# InterfacesB_RGMII_Ethernet.net
KiCad netlist of a schematic drawn in Altium Designer
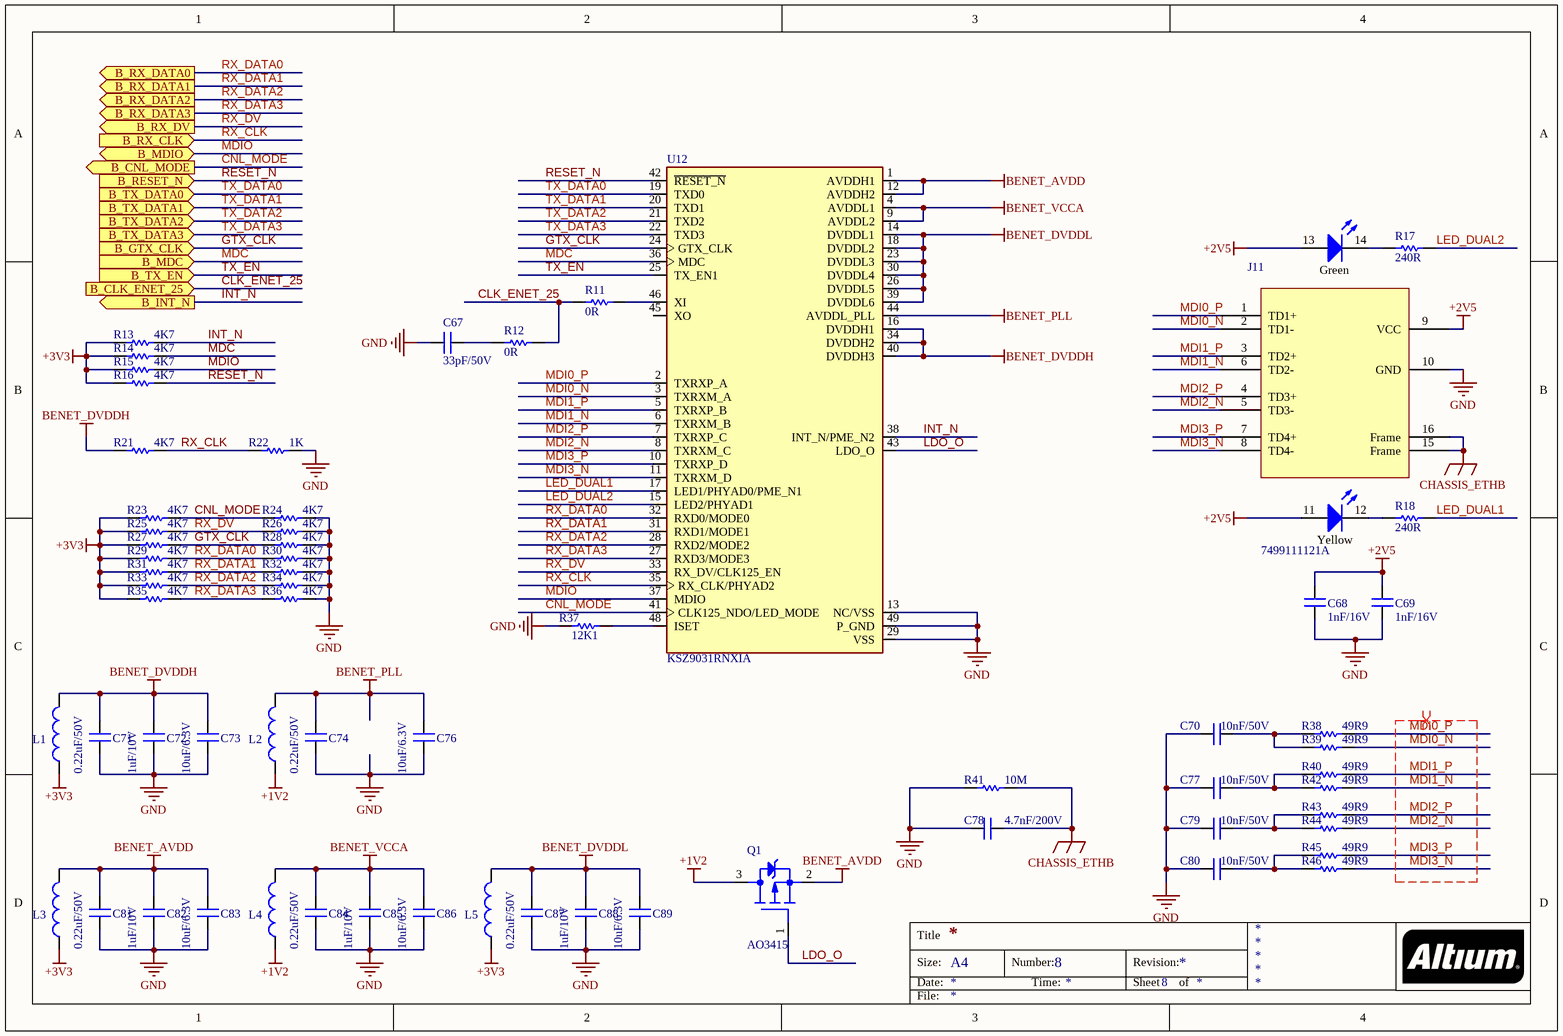
[diagram p0: InterfacesB_RGMII_Ethernet.SchDoc]

(export (version "E")
  (design (tool "Eeschema 10.0.6"))
  (components
    (comp (ref "C67")
      (value "33pF/50V")
      (footprint "CAP_0805")
      (fields (field (name "Comment") "CAP_0805"))
      (libsource (lib "AdapterLib") (part "CAP_0805"))
    )
    (comp (ref "C68")
      (value "1nF/16V")
      (footprint "CAP_0805")
      (fields (field (name "Comment") "CAP_0805"))
      (libsource (lib "AdapterLib") (part "CAP_0805"))
    )
    (comp (ref "C69")
      (value "1nF/16V")
      (footprint "CAP_0805")
      (fields (field (name "Comment") "CAP_0805"))
      (libsource (lib "AdapterLib") (part "CAP_0805"))
    )
    (comp (ref "C70")
      (value "10nF/50V")
      (footprint "CAP_0805")
      (fields (field (name "Comment") "CAP_0805"))
      (libsource (lib "AdapterLib") (part "CAP_0805"))
    )
    (comp (ref "C71")
      (value "0.22uF/50V")
      (footprint "CAP_0805")
      (fields (field (name "Comment") "CAP_0805"))
      (libsource (lib "AdapterLib") (part "CAP_0805"))
    )
    (comp (ref "C72")
      (value "1uF/10V")
      (footprint "CAP_0805")
      (fields (field (name "Comment") "CAP_0805"))
      (libsource (lib "AdapterLib") (part "CAP_0805"))
    )
    (comp (ref "C73")
      (value "10uF/6.3V")
      (footprint "CAP_0805")
      (fields (field (name "Comment") "CAP_0805"))
      (libsource (lib "AdapterLib") (part "CAP_0805"))
    )
    (comp (ref "C74")
      (value "0.22uF/50V")
      (footprint "CAP_0805")
      (fields (field (name "Comment") "CAP_0805"))
      (libsource (lib "AdapterLib") (part "CAP_0805"))
    )
    (comp (ref "C76")
      (value "10uF/6.3V")
      (footprint "CAP_0805")
      (fields (field (name "Comment") "CAP_0805"))
      (libsource (lib "AdapterLib") (part "CAP_0805"))
    )
    (comp (ref "C77")
      (value "10nF/50V")
      (footprint "CAP_0805")
      (fields (field (name "Comment") "CAP_0805"))
      (libsource (lib "AdapterLib") (part "CAP_0805"))
    )
    (comp (ref "C78")
      (value "4.7nF/200V")
      (footprint "CAP_0805")
      (fields (field (name "Comment") "CAP_0805"))
      (libsource (lib "AdapterLib") (part "CAP_0805"))
    )
    (comp (ref "C79")
      (value "10nF/50V")
      (footprint "CAP_0805")
      (fields (field (name "Comment") "CAP_0805"))
      (libsource (lib "AdapterLib") (part "CAP_0805"))
    )
    (comp (ref "C80")
      (value "10nF/50V")
      (footprint "CAP_0805")
      (fields (field (name "Comment") "CAP_0805"))
      (libsource (lib "AdapterLib") (part "CAP_0805"))
    )
    (comp (ref "C81")
      (value "0.22uF/50V")
      (footprint "CAP_0805")
      (fields (field (name "Comment") "CAP_0805"))
      (libsource (lib "AdapterLib") (part "CAP_0805"))
    )
    (comp (ref "C82")
      (value "1uF/10V")
      (footprint "CAP_0805")
      (fields (field (name "Comment") "CAP_0805"))
      (libsource (lib "AdapterLib") (part "CAP_0805"))
    )
    (comp (ref "C83")
      (value "10uF/6.3V")
      (footprint "CAP_0805")
      (fields (field (name "Comment") "CAP_0805"))
      (libsource (lib "AdapterLib") (part "CAP_0805"))
    )
    (comp (ref "C84")
      (value "0.22uF/50V")
      (footprint "CAP_0805")
      (fields (field (name "Comment") "CAP_0805"))
      (libsource (lib "AdapterLib") (part "CAP_0805"))
    )
    (comp (ref "C85")
      (value "1uF/10V")
      (footprint "CAP_0805")
      (fields (field (name "Comment") "CAP_0805"))
      (libsource (lib "AdapterLib") (part "CAP_0805"))
    )
    (comp (ref "C86")
      (value "10uF/6.3V")
      (footprint "CAP_0805")
      (fields (field (name "Comment") "CAP_0805"))
      (libsource (lib "AdapterLib") (part "CAP_0805"))
    )
    (comp (ref "C87")
      (value "0.22uF/50V")
      (footprint "CAP_0805")
      (fields (field (name "Comment") "CAP_0805"))
      (libsource (lib "AdapterLib") (part "CAP_0805"))
    )
    (comp (ref "C88")
      (value "1uF/10V")
      (footprint "CAP_0805")
      (fields (field (name "Comment") "CAP_0805"))
      (libsource (lib "AdapterLib") (part "CAP_0805"))
    )
    (comp (ref "C89")
      (value "10uF/6.3V")
      (footprint "CAP_0805")
      (fields (field (name "Comment") "CAP_0805"))
      (libsource (lib "AdapterLib") (part "CAP_0805"))
    )
    (comp (ref "J11")
      (value "7499111121A")
      (footprint "7499111121A")
      (libsource (lib "AdapterLib") (part "7499111121A"))
    )
    (comp (ref "L1")
      (value "IND_0805")
      (footprint "IND_0805")
      (libsource (lib "AdapterLib") (part "IND_0805"))
    )
    (comp (ref "L2")
      (value "IND_0805")
      (footprint "IND_0805")
      (libsource (lib "AdapterLib") (part "IND_0805"))
    )
    (comp (ref "L3")
      (value "IND_0805")
      (footprint "IND_0805")
      (libsource (lib "AdapterLib") (part "IND_0805"))
    )
    (comp (ref "L4")
      (value "IND_0805")
      (footprint "IND_0805")
      (libsource (lib "AdapterLib") (part "IND_0805"))
    )
    (comp (ref "L5")
      (value "IND_0805")
      (footprint "IND_0805")
      (libsource (lib "AdapterLib") (part "IND_0805"))
    )
    (comp (ref "Q1")
      (value "AO3415")
      (footprint "AO3415")
      (description "20V P-Channel MOSFET")
      (libsource (lib "AdapterLib") (part "AO3415"))
    )
    (comp (ref "R11")
      (value "0R")
      (footprint "RES_0805")
      (fields (field (name "Comment") "RES_0805"))
      (libsource (lib "AdapterLib") (part "RES_0805"))
    )
    (comp (ref "R12")
      (value "0R")
      (footprint "RES_0805")
      (fields (field (name "Comment") "RES_0805"))
      (libsource (lib "AdapterLib") (part "RES_0805"))
    )
    (comp (ref "R13")
      (value "4K7")
      (footprint "RES_0805")
      (fields (field (name "Comment") "RES_0805"))
      (libsource (lib "AdapterLib") (part "RES_0805"))
    )
    (comp (ref "R14")
      (value "4K7")
      (footprint "RES_0805")
      (fields (field (name "Comment") "RES_0805"))
      (libsource (lib "AdapterLib") (part "RES_0805"))
    )
    (comp (ref "R15")
      (value "4K7")
      (footprint "RES_0805")
      (fields (field (name "Comment") "RES_0805"))
      (libsource (lib "AdapterLib") (part "RES_0805"))
    )
    (comp (ref "R16")
      (value "4K7")
      (footprint "RES_0805")
      (fields (field (name "Comment") "RES_0805"))
      (libsource (lib "AdapterLib") (part "RES_0805"))
    )
    (comp (ref "R17")
      (value "240R")
      (footprint "RES_0805")
      (fields (field (name "Comment") "RES_0805"))
      (libsource (lib "AdapterLib") (part "RES_0805"))
    )
    (comp (ref "R18")
      (value "240R")
      (footprint "RES_0805")
      (fields (field (name "Comment") "RES_0805"))
      (libsource (lib "AdapterLib") (part "RES_0805"))
    )
    (comp (ref "R21")
      (value "4K7")
      (footprint "RES_0805")
      (fields (field (name "Comment") "RES_0805"))
      (libsource (lib "AdapterLib") (part "RES_0805"))
    )
    (comp (ref "R22")
      (value "1K")
      (footprint "RES_0805")
      (fields (field (name "Comment") "RES_0805"))
      (libsource (lib "AdapterLib") (part "RES_0805"))
    )
    (comp (ref "R23")
      (value "4K7")
      (footprint "RES_0805")
      (fields (field (name "Comment") "RES_0805"))
      (libsource (lib "AdapterLib") (part "RES_0805"))
    )
    (comp (ref "R24")
      (value "4K7")
      (footprint "RES_0805")
      (fields (field (name "Comment") "RES_0805"))
      (libsource (lib "AdapterLib") (part "RES_0805"))
    )
    (comp (ref "R25")
      (value "4K7")
      (footprint "RES_0805")
      (fields (field (name "Comment") "RES_0805"))
      (libsource (lib "AdapterLib") (part "RES_0805"))
    )
    (comp (ref "R26")
      (value "4K7")
      (footprint "RES_0805")
      (fields (field (name "Comment") "RES_0805"))
      (libsource (lib "AdapterLib") (part "RES_0805"))
    )
    (comp (ref "R27")
      (value "4K7")
      (footprint "RES_0805")
      (fields (field (name "Comment") "RES_0805"))
      (libsource (lib "AdapterLib") (part "RES_0805"))
    )
    (comp (ref "R28")
      (value "4K7")
      (footprint "RES_0805")
      (fields (field (name "Comment") "RES_0805"))
      (libsource (lib "AdapterLib") (part "RES_0805"))
    )
    (comp (ref "R29")
      (value "4K7")
      (footprint "RES_0805")
      (fields (field (name "Comment") "RES_0805"))
      (libsource (lib "AdapterLib") (part "RES_0805"))
    )
    (comp (ref "R30")
      (value "4K7")
      (footprint "RES_0805")
      (fields (field (name "Comment") "RES_0805"))
      (libsource (lib "AdapterLib") (part "RES_0805"))
    )
    (comp (ref "R31")
      (value "4K7")
      (footprint "RES_0805")
      (fields (field (name "Comment") "RES_0805"))
      (libsource (lib "AdapterLib") (part "RES_0805"))
    )
    (comp (ref "R32")
      (value "4K7")
      (footprint "RES_0805")
      (fields (field (name "Comment") "RES_0805"))
      (libsource (lib "AdapterLib") (part "RES_0805"))
    )
    (comp (ref "R33")
      (value "4K7")
      (footprint "RES_0805")
      (fields (field (name "Comment") "RES_0805"))
      (libsource (lib "AdapterLib") (part "RES_0805"))
    )
    (comp (ref "R34")
      (value "4K7")
      (footprint "RES_0805")
      (fields (field (name "Comment") "RES_0805"))
      (libsource (lib "AdapterLib") (part "RES_0805"))
    )
    (comp (ref "R35")
      (value "4K7")
      (footprint "RES_0805")
      (fields (field (name "Comment") "RES_0805"))
      (libsource (lib "AdapterLib") (part "RES_0805"))
    )
    (comp (ref "R36")
      (value "4K7")
      (footprint "RES_0805")
      (fields (field (name "Comment") "RES_0805"))
      (libsource (lib "AdapterLib") (part "RES_0805"))
    )
    (comp (ref "R37")
      (value "12K1")
      (footprint "RES_0805")
      (fields (field (name "Comment") "RES_0805"))
      (libsource (lib "AdapterLib") (part "RES_0805"))
    )
    (comp (ref "R38")
      (value "49R9")
      (footprint "RES_0805")
      (fields (field (name "Comment") "RES_0805"))
      (libsource (lib "AdapterLib") (part "RES_0805"))
    )
    (comp (ref "R39")
      (value "49R9")
      (footprint "RES_0805")
      (fields (field (name "Comment") "RES_0805"))
      (libsource (lib "AdapterLib") (part "RES_0805"))
    )
    (comp (ref "R40")
      (value "49R9")
      (footprint "RES_0805")
      (fields (field (name "Comment") "RES_0805"))
      (libsource (lib "AdapterLib") (part "RES_0805"))
    )
    (comp (ref "R41")
      (value "10M")
      (footprint "RES_0805")
      (fields (field (name "Comment") "RES_0805"))
      (libsource (lib "AdapterLib") (part "RES_0805"))
    )
    (comp (ref "R42")
      (value "49R9")
      (footprint "RES_0805")
      (fields (field (name "Comment") "RES_0805"))
      (libsource (lib "AdapterLib") (part "RES_0805"))
    )
    (comp (ref "R43")
      (value "49R9")
      (footprint "RES_0805")
      (fields (field (name "Comment") "RES_0805"))
      (libsource (lib "AdapterLib") (part "RES_0805"))
    )
    (comp (ref "R44")
      (value "49R9")
      (footprint "RES_0805")
      (fields (field (name "Comment") "RES_0805"))
      (libsource (lib "AdapterLib") (part "RES_0805"))
    )
    (comp (ref "R45")
      (value "49R9")
      (footprint "RES_0805")
      (fields (field (name "Comment") "RES_0805"))
      (libsource (lib "AdapterLib") (part "RES_0805"))
    )
    (comp (ref "R46")
      (value "49R9")
      (footprint "RES_0805")
      (fields (field (name "Comment") "RES_0805"))
      (libsource (lib "AdapterLib") (part "RES_0805"))
    )
    (comp (ref "U12")
      (value "KSZ9031RNXIA")
      (footprint "AdapterLib:KSZ9031RNXIA")
      (description "4/4 Transceiver Full Ethernet 48-QFN _7x7_")
      (fields (field (name "DIGI-KEY_PART_NUMBER") "KSZ9031RNXIA-TR-ND") (field (name "MF") "Microchip"))
      (libsource (lib "AdapterLib") (part "KSZ9031RNXIA"))
    )
  )
  (nets
    (net (code "1") (name "+1V2") (class "Default")
      (node (ref "L2") (pin "1") (pinfunction "1_1") (pintype "passive"))
      (node (ref "L4") (pin "1") (pinfunction "1_1") (pintype "passive"))
      (node (ref "Q1") (pin "3") (pinfunction "D_3") (pintype "passive"))
    )
    (net (code "2") (name "+2V5") (class "Default")
      (node (ref "C68") (pin "2") (pinfunction "2_2") (pintype "passive"))
      (node (ref "C69") (pin "2") (pinfunction "2_2") (pintype "passive"))
      (node (ref "J11") (pin "11") (pinfunction "A_11") (pintype "passive"))
      (node (ref "J11") (pin "13") (pinfunction "A_13") (pintype "passive"))
      (node (ref "J11") (pin "9") (pinfunction "VCC_9") (pintype "passive"))
    )
    (net (code "3") (name "+3V3") (class "Default")
      (node (ref "L1") (pin "1") (pinfunction "1_1") (pintype "passive"))
      (node (ref "L3") (pin "1") (pinfunction "1_1") (pintype "passive"))
      (node (ref "L5") (pin "1") (pinfunction "1_1") (pintype "passive"))
      (node (ref "R13") (pin "2") (pinfunction "2_2") (pintype "passive"))
      (node (ref "R14") (pin "2") (pinfunction "2_2") (pintype "passive"))
      (node (ref "R15") (pin "2") (pinfunction "2_2") (pintype "passive"))
      (node (ref "R16") (pin "2") (pinfunction "2_2") (pintype "passive"))
      (node (ref "R23") (pin "2") (pinfunction "2_2") (pintype "passive"))
      (node (ref "R25") (pin "2") (pinfunction "2_2") (pintype "passive"))
      (node (ref "R27") (pin "2") (pinfunction "2_2") (pintype "passive"))
      (node (ref "R29") (pin "2") (pinfunction "2_2") (pintype "passive"))
      (node (ref "R31") (pin "2") (pinfunction "2_2") (pintype "passive"))
      (node (ref "R33") (pin "2") (pinfunction "2_2") (pintype "passive"))
      (node (ref "R35") (pin "2") (pinfunction "2_2") (pintype "passive"))
    )
    (net (code "4") (name "/CLK_ENET_25") (class "Default")
      (node (ref "R11") (pin "2") (pinfunction "2_2") (pintype "passive"))
      (node (ref "R12") (pin "2") (pinfunction "2_2") (pintype "passive"))
    )
    (net (code "5") (name "/CNL_MODE") (class "Default")
      (node (ref "R23") (pin "1") (pinfunction "1_1") (pintype "passive"))
      (node (ref "R24") (pin "2") (pinfunction "2_2") (pintype "passive"))
      (node (ref "U12") (pin "41") (pinfunction "CLK125_NDO/LED_MODE_41") (pintype "passive"))
    )
    (net (code "6") (name "/GTX_CLK") (class "Default")
      (node (ref "R27") (pin "1") (pinfunction "1_1") (pintype "passive"))
      (node (ref "R28") (pin "2") (pinfunction "2_2") (pintype "passive"))
      (node (ref "U12") (pin "24") (pinfunction "GTX_CLK_24") (pintype "passive"))
    )
    (net (code "7") (name "/INT_N") (class "Default")
      (node (ref "R13") (pin "1") (pinfunction "1_1") (pintype "passive"))
      (node (ref "U12") (pin "38") (pinfunction "INT_N/PME_N2_38") (pintype "passive"))
    )
    (net (code "8") (name "/LDO_O") (class "Default")
      (node (ref "Q1") (pin "1") (pinfunction "G_1") (pintype "passive"))
      (node (ref "U12") (pin "43") (pinfunction "LDO_O_43") (pintype "passive"))
    )
    (net (code "9") (name "/LED_DUAL1") (class "Default")
      (node (ref "R18") (pin "2") (pinfunction "2_2") (pintype "passive"))
      (node (ref "U12") (pin "17") (pinfunction "LED1/PHYAD0/PME_N1_17") (pintype "passive"))
    )
    (net (code "10") (name "/LED_DUAL2") (class "Default")
      (node (ref "R17") (pin "2") (pinfunction "2_2") (pintype "passive"))
      (node (ref "U12") (pin "15") (pinfunction "LED2/PHYAD1_15") (pintype "passive"))
    )
    (net (code "11") (name "/MDC") (class "Default")
      (node (ref "R14") (pin "1") (pinfunction "1_1") (pintype "passive"))
      (node (ref "U12") (pin "36") (pinfunction "MDC_36") (pintype "passive"))
    )
    (net (code "12") (name "/MDI0_N") (class "Default")
      (node (ref "J11") (pin "2") (pinfunction "TD1-_2") (pintype "passive"))
      (node (ref "R39") (pin "2") (pinfunction "2_2") (pintype "passive"))
      (node (ref "U12") (pin "3") (pinfunction "TXRXM_A_3") (pintype "passive"))
    )
    (net (code "13") (name "/MDI0_P") (class "Default")
      (node (ref "J11") (pin "1") (pinfunction "TD1+_1") (pintype "passive"))
      (node (ref "R38") (pin "2") (pinfunction "2_2") (pintype "passive"))
      (node (ref "U12") (pin "2") (pinfunction "TXRXP_A_2") (pintype "passive"))
    )
    (net (code "14") (name "/MDI1_N") (class "Default")
      (node (ref "J11") (pin "6") (pinfunction "TD2-_6") (pintype "passive"))
      (node (ref "R42") (pin "2") (pinfunction "2_2") (pintype "passive"))
      (node (ref "U12") (pin "6") (pinfunction "TXRXM_B_6") (pintype "passive"))
    )
    (net (code "15") (name "/MDI1_P") (class "Default")
      (node (ref "J11") (pin "3") (pinfunction "TD2+_3") (pintype "passive"))
      (node (ref "R40") (pin "2") (pinfunction "2_2") (pintype "passive"))
      (node (ref "U12") (pin "5") (pinfunction "TXRXP_B_5") (pintype "passive"))
    )
    (net (code "16") (name "/MDI2_N") (class "Default")
      (node (ref "J11") (pin "5") (pinfunction "TD3-_5") (pintype "passive"))
      (node (ref "R44") (pin "2") (pinfunction "2_2") (pintype "passive"))
      (node (ref "U12") (pin "8") (pinfunction "TXRXM_C_8") (pintype "passive"))
    )
    (net (code "17") (name "/MDI2_P") (class "Default")
      (node (ref "J11") (pin "4") (pinfunction "TD3+_4") (pintype "passive"))
      (node (ref "R43") (pin "2") (pinfunction "2_2") (pintype "passive"))
      (node (ref "U12") (pin "7") (pinfunction "TXRXP_C_7") (pintype "passive"))
    )
    (net (code "18") (name "/MDI3_N") (class "Default")
      (node (ref "J11") (pin "8") (pinfunction "TD4-_8") (pintype "passive"))
      (node (ref "R46") (pin "2") (pinfunction "2_2") (pintype "passive"))
      (node (ref "U12") (pin "11") (pinfunction "TXRXM_D_11") (pintype "passive"))
    )
    (net (code "19") (name "/MDI3_P") (class "Default")
      (node (ref "J11") (pin "7") (pinfunction "TD4+_7") (pintype "passive"))
      (node (ref "R45") (pin "2") (pinfunction "2_2") (pintype "passive"))
      (node (ref "U12") (pin "10") (pinfunction "TXRXP_D_10") (pintype "passive"))
    )
    (net (code "20") (name "/MDIO") (class "Default")
      (node (ref "R15") (pin "1") (pinfunction "1_1") (pintype "passive"))
      (node (ref "U12") (pin "37") (pinfunction "MDIO_37") (pintype "passive"))
    )
    (net (code "21") (name "/RESET_N") (class "Default")
      (node (ref "R16") (pin "1") (pinfunction "1_1") (pintype "passive"))
      (node (ref "U12") (pin "42") (pinfunction "~{RESET_N}_42") (pintype "passive"))
    )
    (net (code "22") (name "/RX_CLK") (class "Default")
      (node (ref "R21") (pin "1") (pinfunction "1_1") (pintype "passive"))
      (node (ref "R22") (pin "2") (pinfunction "2_2") (pintype "passive"))
      (node (ref "U12") (pin "35") (pinfunction "RX_CLK/PHYAD2_35") (pintype "passive"))
    )
    (net (code "23") (name "/RX_DATA0") (class "Default")
      (node (ref "R29") (pin "1") (pinfunction "1_1") (pintype "passive"))
      (node (ref "R30") (pin "2") (pinfunction "2_2") (pintype "passive"))
      (node (ref "U12") (pin "32") (pinfunction "RXD0/MODE0_32") (pintype "passive"))
    )
    (net (code "24") (name "/RX_DATA1") (class "Default")
      (node (ref "R31") (pin "1") (pinfunction "1_1") (pintype "passive"))
      (node (ref "R32") (pin "2") (pinfunction "2_2") (pintype "passive"))
      (node (ref "U12") (pin "31") (pinfunction "RXD1/MODE1_31") (pintype "passive"))
    )
    (net (code "25") (name "/RX_DATA2") (class "Default")
      (node (ref "R33") (pin "1") (pinfunction "1_1") (pintype "passive"))
      (node (ref "R34") (pin "2") (pinfunction "2_2") (pintype "passive"))
      (node (ref "U12") (pin "28") (pinfunction "RXD2/MODE2_28") (pintype "passive"))
    )
    (net (code "26") (name "/RX_DATA3") (class "Default")
      (node (ref "R35") (pin "1") (pinfunction "1_1") (pintype "passive"))
      (node (ref "R36") (pin "2") (pinfunction "2_2") (pintype "passive"))
      (node (ref "U12") (pin "27") (pinfunction "RXD3/MODE3_27") (pintype "passive"))
    )
    (net (code "27") (name "/RX_DV") (class "Default")
      (node (ref "R25") (pin "1") (pinfunction "1_1") (pintype "passive"))
      (node (ref "R26") (pin "2") (pinfunction "2_2") (pintype "passive"))
      (node (ref "U12") (pin "33") (pinfunction "RX_DV/CLK125_EN_33") (pintype "passive"))
    )
    (net (code "28") (name "/TX_DATA0") (class "Default")
      (node (ref "U12") (pin "19") (pinfunction "TXD0_19") (pintype "passive"))
    )
    (net (code "29") (name "/TX_DATA1") (class "Default")
      (node (ref "U12") (pin "20") (pinfunction "TXD1_20") (pintype "passive"))
    )
    (net (code "30") (name "/TX_DATA2") (class "Default")
      (node (ref "U12") (pin "21") (pinfunction "TXD2_21") (pintype "passive"))
    )
    (net (code "31") (name "/TX_DATA3") (class "Default")
      (node (ref "U12") (pin "22") (pinfunction "TXD3_22") (pintype "passive"))
    )
    (net (code "32") (name "/TX_EN") (class "Default")
      (node (ref "U12") (pin "25") (pinfunction "TX_EN1_25") (pintype "passive"))
    )
    (net (code "33") (name "BENET_AVDD") (class "Default")
      (node (ref "C81") (pin "2") (pinfunction "2_2") (pintype "passive"))
      (node (ref "C82") (pin "2") (pinfunction "2_2") (pintype "passive"))
      (node (ref "C83") (pin "2") (pinfunction "2_2") (pintype "passive"))
      (node (ref "L3") (pin "2") (pinfunction "2_2") (pintype "passive"))
      (node (ref "Q1") (pin "2") (pinfunction "S_2") (pintype "passive"))
      (node (ref "U12") (pin "1") (pinfunction "AVDDH1_1") (pintype "passive"))
      (node (ref "U12") (pin "12") (pinfunction "AVDDH2_12") (pintype "passive"))
    )
    (net (code "34") (name "BENET_DVDDH") (class "Default")
      (node (ref "C71") (pin "2") (pinfunction "2_2") (pintype "passive"))
      (node (ref "C72") (pin "2") (pinfunction "2_2") (pintype "passive"))
      (node (ref "C73") (pin "2") (pinfunction "2_2") (pintype "passive"))
      (node (ref "L1") (pin "2") (pinfunction "2_2") (pintype "passive"))
      (node (ref "R21") (pin "2") (pinfunction "2_2") (pintype "passive"))
      (node (ref "U12") (pin "16") (pinfunction "DVDDH1_16") (pintype "passive"))
      (node (ref "U12") (pin "34") (pinfunction "DVDDH2_34") (pintype "passive"))
      (node (ref "U12") (pin "40") (pinfunction "DVDDH3_40") (pintype "passive"))
    )
    (net (code "35") (name "BENET_DVDDL") (class "Default")
      (node (ref "C87") (pin "2") (pinfunction "2_2") (pintype "passive"))
      (node (ref "C88") (pin "2") (pinfunction "2_2") (pintype "passive"))
      (node (ref "C89") (pin "2") (pinfunction "2_2") (pintype "passive"))
      (node (ref "L5") (pin "2") (pinfunction "2_2") (pintype "passive"))
      (node (ref "U12") (pin "14") (pinfunction "DVDDL1_14") (pintype "passive"))
      (node (ref "U12") (pin "18") (pinfunction "DVDDL2_18") (pintype "passive"))
      (node (ref "U12") (pin "23") (pinfunction "DVDDL3_23") (pintype "passive"))
      (node (ref "U12") (pin "26") (pinfunction "DVDDL5_26") (pintype "passive"))
      (node (ref "U12") (pin "30") (pinfunction "DVDDL4_30") (pintype "passive"))
      (node (ref "U12") (pin "39") (pinfunction "DVDDL6_39") (pintype "passive"))
    )
    (net (code "36") (name "BENET_PLL") (class "Default")
      (node (ref "C74") (pin "2") (pinfunction "2_2") (pintype "passive"))
      (node (ref "C76") (pin "2") (pinfunction "2_2") (pintype "passive"))
      (node (ref "L2") (pin "2") (pinfunction "2_2") (pintype "passive"))
      (node (ref "U12") (pin "44") (pinfunction "AVDDL_PLL_44") (pintype "passive"))
    )
    (net (code "37") (name "BENET_VCCA") (class "Default")
      (node (ref "C84") (pin "2") (pinfunction "2_2") (pintype "passive"))
      (node (ref "C85") (pin "2") (pinfunction "2_2") (pintype "passive"))
      (node (ref "C86") (pin "2") (pinfunction "2_2") (pintype "passive"))
      (node (ref "L4") (pin "2") (pinfunction "2_2") (pintype "passive"))
      (node (ref "U12") (pin "4") (pinfunction "AVDDL1_4") (pintype "passive"))
      (node (ref "U12") (pin "9") (pinfunction "AVDDL2_9") (pintype "passive"))
    )
    (net (code "38") (name "CHASSIS_ETHB") (class "Default")
      (node (ref "C78") (pin "1") (pinfunction "1_1") (pintype "passive"))
      (node (ref "J11") (pin "15") (pinfunction "Frame_15") (pintype "passive"))
      (node (ref "J11") (pin "16") (pinfunction "Frame_16") (pintype "passive"))
      (node (ref "R41") (pin "1") (pinfunction "1_1") (pintype "passive"))
    )
    (net (code "39") (name "GND") (class "Default")
      (node (ref "C67") (pin "2") (pinfunction "2_2") (pintype "passive"))
      (node (ref "C68") (pin "1") (pinfunction "1_1") (pintype "passive"))
      (node (ref "C69") (pin "1") (pinfunction "1_1") (pintype "passive"))
      (node (ref "C70") (pin "2") (pinfunction "2_2") (pintype "passive"))
      (node (ref "C71") (pin "1") (pinfunction "1_1") (pintype "passive"))
      (node (ref "C72") (pin "1") (pinfunction "1_1") (pintype "passive"))
      (node (ref "C73") (pin "1") (pinfunction "1_1") (pintype "passive"))
      (node (ref "C74") (pin "1") (pinfunction "1_1") (pintype "passive"))
      (node (ref "C76") (pin "1") (pinfunction "1_1") (pintype "passive"))
      (node (ref "C77") (pin "2") (pinfunction "2_2") (pintype "passive"))
      (node (ref "C78") (pin "2") (pinfunction "2_2") (pintype "passive"))
      (node (ref "C79") (pin "2") (pinfunction "2_2") (pintype "passive"))
      (node (ref "C80") (pin "2") (pinfunction "2_2") (pintype "passive"))
      (node (ref "C81") (pin "1") (pinfunction "1_1") (pintype "passive"))
      (node (ref "C82") (pin "1") (pinfunction "1_1") (pintype "passive"))
      (node (ref "C83") (pin "1") (pinfunction "1_1") (pintype "passive"))
      (node (ref "C84") (pin "1") (pinfunction "1_1") (pintype "passive"))
      (node (ref "C85") (pin "1") (pinfunction "1_1") (pintype "passive"))
      (node (ref "C86") (pin "1") (pinfunction "1_1") (pintype "passive"))
      (node (ref "C87") (pin "1") (pinfunction "1_1") (pintype "passive"))
      (node (ref "C88") (pin "1") (pinfunction "1_1") (pintype "passive"))
      (node (ref "C89") (pin "1") (pinfunction "1_1") (pintype "passive"))
      (node (ref "J11") (pin "10") (pinfunction "GND_10") (pintype "passive"))
      (node (ref "R22") (pin "1") (pinfunction "1_1") (pintype "passive"))
      (node (ref "R24") (pin "1") (pinfunction "1_1") (pintype "passive"))
      (node (ref "R26") (pin "1") (pinfunction "1_1") (pintype "passive"))
      (node (ref "R28") (pin "1") (pinfunction "1_1") (pintype "passive"))
      (node (ref "R30") (pin "1") (pinfunction "1_1") (pintype "passive"))
      (node (ref "R32") (pin "1") (pinfunction "1_1") (pintype "passive"))
      (node (ref "R34") (pin "1") (pinfunction "1_1") (pintype "passive"))
      (node (ref "R36") (pin "1") (pinfunction "1_1") (pintype "passive"))
      (node (ref "R37") (pin "1") (pinfunction "1_1") (pintype "passive"))
      (node (ref "R41") (pin "2") (pinfunction "2_2") (pintype "passive"))
      (node (ref "U12") (pin "13") (pinfunction "NC/VSS_13") (pintype "passive"))
      (node (ref "U12") (pin "29") (pinfunction "VSS_29") (pintype "passive"))
      (node (ref "U12") (pin "49") (pinfunction "P_GND_49") (pintype "passive"))
    )
    (net (code "40") (name "Net-(C67-Pad1)") (class "Default")
      (node (ref "C67") (pin "1") (pinfunction "1_1") (pintype "passive"))
      (node (ref "R12") (pin "1") (pinfunction "1_1") (pintype "passive"))
    )
    (net (code "41") (name "Net-(C70-Pad1)") (class "Default")
      (node (ref "C70") (pin "1") (pinfunction "1_1") (pintype "passive"))
      (node (ref "R38") (pin "1") (pinfunction "1_1") (pintype "passive"))
      (node (ref "R39") (pin "1") (pinfunction "1_1") (pintype "passive"))
    )
    (net (code "42") (name "Net-(C77-Pad1)") (class "Default")
      (node (ref "C77") (pin "1") (pinfunction "1_1") (pintype "passive"))
      (node (ref "R40") (pin "1") (pinfunction "1_1") (pintype "passive"))
      (node (ref "R42") (pin "1") (pinfunction "1_1") (pintype "passive"))
    )
    (net (code "43") (name "Net-(C79-Pad1)") (class "Default")
      (node (ref "C79") (pin "1") (pinfunction "1_1") (pintype "passive"))
      (node (ref "R43") (pin "1") (pinfunction "1_1") (pintype "passive"))
      (node (ref "R44") (pin "1") (pinfunction "1_1") (pintype "passive"))
    )
    (net (code "44") (name "Net-(C80-Pad1)") (class "Default")
      (node (ref "C80") (pin "1") (pinfunction "1_1") (pintype "passive"))
      (node (ref "R45") (pin "1") (pinfunction "1_1") (pintype "passive"))
      (node (ref "R46") (pin "1") (pinfunction "1_1") (pintype "passive"))
    )
    (net (code "45") (name "Net-(J11-K-Pad12)") (class "Default")
      (node (ref "J11") (pin "12") (pinfunction "K_12") (pintype "passive"))
      (node (ref "R18") (pin "1") (pinfunction "1_1") (pintype "passive"))
    )
    (net (code "46") (name "Net-(J11-K-Pad14)") (class "Default")
      (node (ref "J11") (pin "14") (pinfunction "K_14") (pintype "passive"))
      (node (ref "R17") (pin "1") (pinfunction "1_1") (pintype "passive"))
    )
    (net (code "47") (name "Net-(U12-ISET)") (class "Default")
      (node (ref "R37") (pin "2") (pinfunction "2_2") (pintype "passive"))
      (node (ref "U12") (pin "48") (pinfunction "ISET_48") (pintype "passive"))
    )
    (net (code "48") (name "Net-(U12-XI)") (class "Default")
      (node (ref "R11") (pin "1") (pinfunction "1_1") (pintype "passive"))
      (node (ref "U12") (pin "46") (pinfunction "XI_46") (pintype "passive"))
    )
    (net (code "49") (name "unconnected-(U12-XO-Pad45)") (class "Default")
      (node (ref "U12") (pin "45") (pinfunction "XO_45") (pintype "passive"))
    )
  )
)
